# 4_half_bridge.net
KiCad netlist of a schematic drawn in Altium Designer
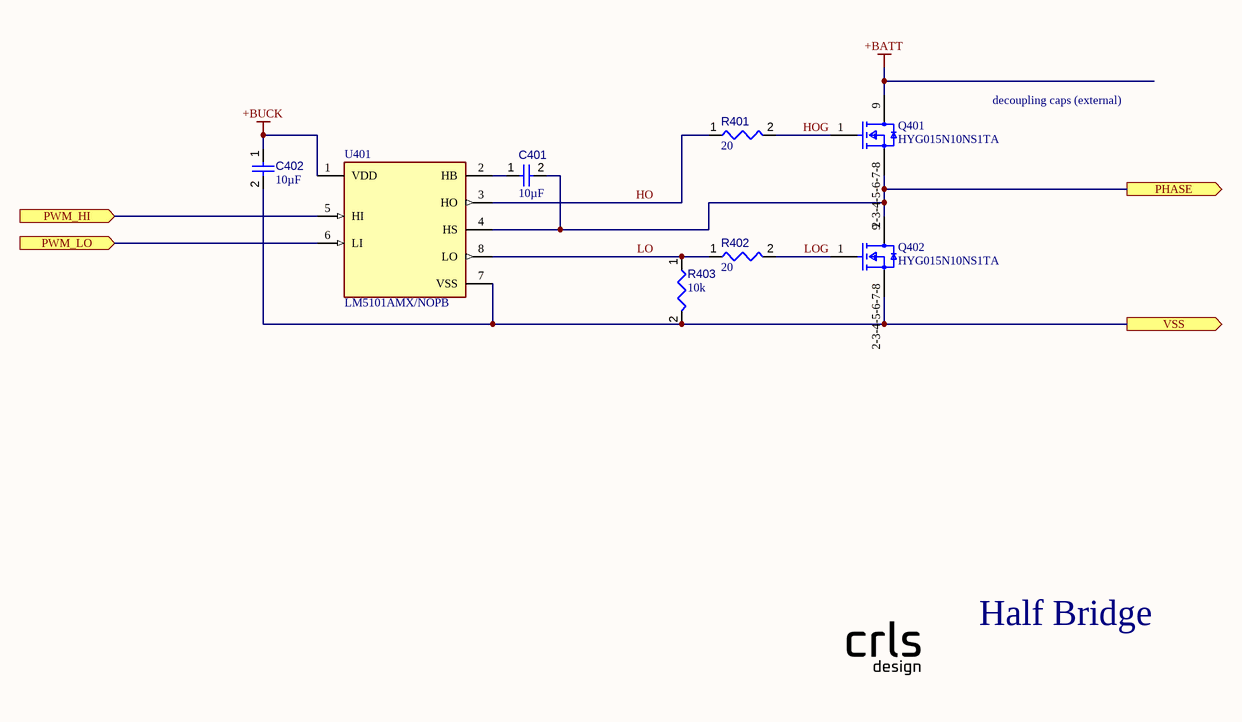
[diagram p0: 4 half bridge.SchDoc]

(export (version "E")
  (design (tool "Eeschema 10.0.6"))
  (components
    (comp (ref "C401")
      (value "10µF")
      (footprint "CAPC0603(1608)100_L")
      (description "Chip Capacitor, 10µF +/-20%, 10V, 0603, Thickness 1 mm")
      (fields (field (name "TOLERANCE") "10%") (field (name "Comment") "Capacitor 10µF +/-20% 10V 0603"))
      (libsource (lib "UBC Uncrewed Aircraft Systems") (part "CAP-NP-2"))
    )
    (comp (ref "C402")
      (value "10µF")
      (footprint "CAPC0603(1608)100_L")
      (description "Chip Capacitor, 10µF +/-20%, 10V, 0603, Thickness 1 mm")
      (fields (field (name "TOLERANCE") "10%") (field (name "Comment") "Capacitor 10µF +/-20% 10V 0603"))
      (libsource (lib "UBC Uncrewed Aircraft Systems") (part "CAP-NP-2"))
    )
    (comp (ref "Q401")
      (value "HYG015N10NS1TA")
      (footprint "FP-PG-HSOF-8-MFG")
      (description "HYG015N10NS1TA 100V, N-Ch, 1.2 mΩ max, Automotive MOSFET, TOLL, OptiMOS™-5, PG-HSOF-8, RoHS")
      (libsource (lib "Altium Content Vault") (part "c1dc76d428a3a1967873c3bde523568"))
    )
    (comp (ref "Q402")
      (value "HYG015N10NS1TA")
      (footprint "FP-PG-HSOF-8-MFG")
      (description "HYG015N10NS1TA 100V, N-Ch, 1.2 mΩ max, Automotive MOSFET, TOLL, OptiMOS™-5, PG-HSOF-8, RoHS")
      (libsource (lib "Altium Content Vault") (part "c1dc76d428a3a1967873c3bde523568"))
    )
    (comp (ref "R401")
      (value "20")
      (footprint "RESC0603(1608)_L")
      (description "Chip Resistor, 20 Ohms, +/-5 %, 0.1 W, -55 to 155 degC, 0603")
      (fields (field (name "TOLERANCE") "5%") (field (name "POWER") "100mW"))
      (libsource (lib "UBC Uncrewed Aircraft Systems") (part "RES-2"))
    )
    (comp (ref "R402")
      (value "20")
      (footprint "RESC0603(1608)_L")
      (description "Chip Resistor, 20 Ohms, +/-5 %, 0.1 W, -55 to 155 degC, 0603")
      (fields (field (name "TOLERANCE") "5%") (field (name "POWER") "100mW"))
      (libsource (lib "UBC Uncrewed Aircraft Systems") (part "RES-2"))
    )
    (comp (ref "R403")
      (value "10k")
      (footprint "RESC0402(1005)_L")
      (description "Chip Resistor, 10 kOhms, +/-1 %, 63 mW, -55 to 125 degC, 0402")
      (fields (field (name "POWER") "63mW") (field (name "TOLERANCE") "1%"))
      (libsource (lib "UBC Uncrewed Aircraft Systems") (part "RES-2"))
    )
    (comp (ref "U401")
      (value "LM5101AMX/NOPB")
      (footprint "FP-D0008A-MFG")
      (description "IC GATE DRVR HALF-BRIDGE 8SOIC")
      (libsource (lib "Altium Content Vault") (part "cccb75fdea50f8568ff7d6a99a5b102"))
    )
  )
  (nets
    (net (code "1") (name "+BATT") (class "Default")
      (node (ref "Q401") (pin "9") (pinfunction "D_9") (pintype "passive"))
    )
    (net (code "2") (name "+BUCK") (class "Default")
      (node (ref "C402") (pin "1") (pinfunction "1_1") (pintype "passive"))
      (node (ref "U401") (pin "1") (pinfunction "VDD_1") (pintype "power_in"))
    )
    (net (code "3") (name "/HO") (class "Default")
      (node (ref "R401") (pin "1") (pinfunction "1_1") (pintype "passive"))
      (node (ref "U401") (pin "3") (pinfunction "HO_3") (pintype "output"))
    )
    (net (code "4") (name "/HOG") (class "Default")
      (node (ref "Q401") (pin "1") (pinfunction "G_1") (pintype "passive"))
      (node (ref "R401") (pin "2") (pinfunction "2_2") (pintype "passive"))
    )
    (net (code "5") (name "/LO") (class "Default")
      (node (ref "R402") (pin "1") (pinfunction "1_1") (pintype "passive"))
      (node (ref "R403") (pin "1") (pinfunction "1_1") (pintype "passive"))
      (node (ref "U401") (pin "8") (pinfunction "LO_8") (pintype "output"))
    )
    (net (code "6") (name "/LOG") (class "Default")
      (node (ref "Q402") (pin "1") (pinfunction "G_1") (pintype "passive"))
      (node (ref "R402") (pin "2") (pinfunction "2_2") (pintype "passive"))
    )
    (net (code "7") (name "/PHASE") (class "Default")
      (node (ref "C401") (pin "2") (pinfunction "2_2") (pintype "passive"))
      (node (ref "Q401") (pin "2-3-4-5-6-7-8") (pinfunction "S_2-3-4-5-6-7-8") (pintype "passive"))
      (node (ref "Q402") (pin "9") (pinfunction "D_9") (pintype "passive"))
      (node (ref "U401") (pin "4") (pinfunction "HS_4") (pintype "passive"))
    )
    (net (code "8") (name "/PWM_HI") (class "Default")
      (node (ref "U401") (pin "5") (pinfunction "HI_5") (pintype "input"))
    )
    (net (code "9") (name "/PWM_LO") (class "Default")
      (node (ref "U401") (pin "6") (pinfunction "LI_6") (pintype "input"))
    )
    (net (code "10") (name "/VSS") (class "Default")
      (node (ref "C402") (pin "2") (pinfunction "2_2") (pintype "passive"))
      (node (ref "Q402") (pin "2-3-4-5-6-7-8") (pinfunction "S_2-3-4-5-6-7-8") (pintype "passive"))
      (node (ref "R403") (pin "2") (pinfunction "2_2") (pintype "passive"))
      (node (ref "U401") (pin "7") (pinfunction "VSS_7") (pintype "power_in"))
    )
    (net (code "11") (name "Net-(U401-HB)") (class "Default")
      (node (ref "C401") (pin "1") (pinfunction "1_1") (pintype "passive"))
      (node (ref "U401") (pin "2") (pinfunction "HB_2") (pintype "power_in"))
    )
  )
)
